# VREG_RT9166-12PVL_with_EN.net
KiCad netlist of a schematic drawn in Altium Designer
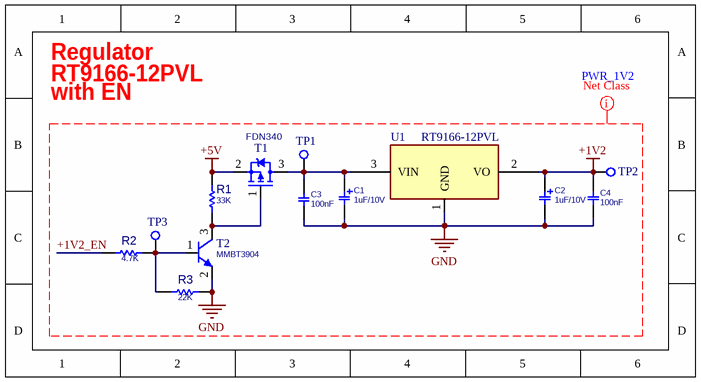
[diagram p0: VREG RT9166-12PVL with EN.SchDoc]

(export (version "E")
  (design (tool "Eeschema 10.0.6"))
  (components
    (comp (ref "C1")
      (value "1uF/10V")
      (footprint "C_TN_A")
      (description "CAP, SMD, TAN")
      (libsource (lib "PW Components 97_492") (part "CAP_SMD_TAN"))
    )
    (comp (ref "C2")
      (value "1uF/10V")
      (footprint "C_TN_A")
      (description "CAP, SMD, TAN")
      (libsource (lib "PW Components 97_492") (part "CAP_SMD_TAN"))
    )
    (comp (ref "C3")
      (value "100nF")
      (footprint "C0603S")
      (description "CAP, SMD, MLCC")
      (fields (field (name "MANF_P#") "MANF_PART#") (field (name "MANF") "Murata"))
      (libsource (lib "Passive") (part "CAP_SMD_MLCC"))
    )
    (comp (ref "C4")
      (value "100nF")
      (footprint "C0603S")
      (description "CAP, SMD, MLCC")
      (fields (field (name "MANF_P#") "MANF_PART#") (field (name "MANF") "Murata"))
      (libsource (lib "Passive") (part "CAP_SMD_MLCC"))
    )
    (comp (ref "R1")
      (value "33K")
      (footprint "R0603S")
      (description "RES, SMD")
      (fields (field (name "MANF_P#") "RK73H1ETTP4701F") (field (name "MANF") "KOA SPEER"))
      (libsource (lib "Passive") (part "RES_SMD"))
    )
    (comp (ref "R2")
      (value "4.7K")
      (footprint "R0603S")
      (description "RES, SMD")
      (fields (field (name "MANF_P#") "RK73H1ETTP4701F") (field (name "MANF") "KOA SPEER"))
      (libsource (lib "Passive") (part "RES_SMD"))
    )
    (comp (ref "R3")
      (value "22K")
      (footprint "R0603S")
      (description "RES, SMD")
      (fields (field (name "MANF_P#") "RK73H1ETTP4701F") (field (name "MANF") "KOA SPEER"))
      (libsource (lib "Passive") (part "RES_SMD"))
    )
    (comp (ref "T1")
      (value "FDN340")
      (footprint "SOT23_3")
      (description "MOSFET SMD P-CH 20V 2A")
      (fields (field (name "MANF_P#") "FDN360"))
      (libsource (lib "Transistor FET") (part "MOSP_FDN340_SOT23"))
    )
    (comp (ref "T2")
      (value "MMBT3904")
      (footprint "SOT23_3")
      (description "BJT, NPN, 40V, 0.2A, SMD, SOT23")
      (fields (field (name "MANF") "Diodes, NXP, FAIRCHILD, ON"))
      (libsource (lib "Transistor BJT") (part "NPN_MMBT3904_SOT23"))
    )
    (comp (ref "TP1")
      (value "Test Point")
      (footprint "TPSMD_C1")
      (libsource (lib "Passives") (part "Test Point"))
    )
    (comp (ref "TP2")
      (value "Test Point")
      (footprint "TPSMD_C1")
      (libsource (lib "Passives") (part "Test Point"))
    )
    (comp (ref "TP3")
      (value "Test Point")
      (footprint "TPSMD_C1")
      (libsource (lib "Passives") (part "Test Point"))
    )
    (comp (ref "U1")
      (value "RT9166-12PVL")
      (footprint "SOT23_3")
      (description "REG, Linear, Fixed, 1.2v, 0.3A/0.6A, SOT23")
      (fields (field (name "MANF") "TI"))
      (libsource (lib "PW Components 97_481") (part "VREG_RT9166A-12PVL_SOT23"))
    )
  )
  (nets
    (net (code "1") (name "+1V2") (class "Default")
      (node (ref "C2") (pin "1") (pinfunction "1_1") (pintype "passive"))
      (node (ref "C4") (pin "1") (pinfunction "1_1") (pintype "passive"))
      (node (ref "TP2") (pin "1") (pinfunction "TP_1") (pintype "passive"))
      (node (ref "U1") (pin "2") (pinfunction "VO_2") (pintype "passive"))
    )
    (net (code "2") (name "+5V") (class "Default")
      (node (ref "R1") (pin "2") (pinfunction "2_2") (pintype "passive"))
      (node (ref "T1") (pin "2") (pinfunction "S_2") (pintype "passive"))
    )
    (net (code "3") (name "/+1V2_EN") (class "Default")
      (node (ref "R2") (pin "2") (pinfunction "2_2") (pintype "passive"))
    )
    (net (code "4") (name "GND") (class "Default")
      (node (ref "C1") (pin "2") (pinfunction "2_2") (pintype "passive"))
      (node (ref "C2") (pin "2") (pinfunction "2_2") (pintype "passive"))
      (node (ref "C3") (pin "2") (pinfunction "2_2") (pintype "passive"))
      (node (ref "C4") (pin "2") (pinfunction "2_2") (pintype "passive"))
      (node (ref "R3") (pin "1") (pinfunction "1_1") (pintype "passive"))
      (node (ref "T2") (pin "2") (pinfunction "E_2") (pintype "passive"))
      (node (ref "U1") (pin "1") (pinfunction "GND_1") (pintype "passive"))
    )
    (net (code "5") (name "Net-(T1-D)") (class "Default")
      (node (ref "C1") (pin "1") (pinfunction "1_1") (pintype "passive"))
      (node (ref "C3") (pin "1") (pinfunction "1_1") (pintype "passive"))
      (node (ref "T1") (pin "3") (pinfunction "D_3") (pintype "passive"))
      (node (ref "TP1") (pin "1") (pinfunction "TP_1") (pintype "passive"))
      (node (ref "U1") (pin "3") (pinfunction "VIN_3") (pintype "passive"))
    )
    (net (code "6") (name "Net-(T1-G)") (class "Default")
      (node (ref "R1") (pin "1") (pinfunction "1_1") (pintype "passive"))
      (node (ref "T1") (pin "1") (pinfunction "G_1") (pintype "passive"))
      (node (ref "T2") (pin "3") (pinfunction "C_3") (pintype "passive"))
    )
    (net (code "7") (name "Net-(T2-B)") (class "Default")
      (node (ref "R2") (pin "1") (pinfunction "1_1") (pintype "passive"))
      (node (ref "R3") (pin "2") (pinfunction "2_2") (pintype "passive"))
      (node (ref "T2") (pin "1") (pinfunction "B_1") (pintype "passive"))
      (node (ref "TP3") (pin "1") (pinfunction "TP_1") (pintype "passive"))
    )
  )
)
